# taller_2.net
KiCad netlist of a schematic drawn in EAGLE
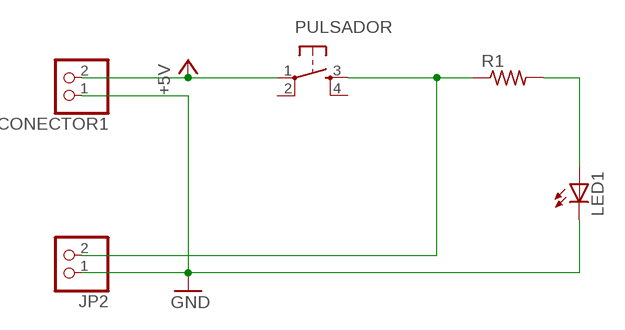
[diagram p0: schematic, sheet 1]

(export (version "E")
  (design (tool "Eeschema 10.0.6"))
  (components
    (comp (ref "CONECTOR1")
      (value "PINHD-1X2/90")
      (footprint "eagle-import:1X02_90")
      (libsource (lib "eagle-import") (part "PINHD-1X2/90"))
    )
    (comp (ref "JP2")
      (value "PINHD-1X2/90")
      (footprint "eagle-import:1X02_90")
      (libsource (lib "eagle-import") (part "PINHD-1X2/90"))
    )
    (comp (ref "LED1")
      (value "LED5MM")
      (footprint "eagle-import:LED5MM")
      (libsource (lib "eagle-import") (part "LED5MM"))
    )
    (comp (ref "PULSADOR")
      (value "TAC_SWITCHPTH")
      (footprint "eagle-import:TACTILE-PTH")
      (libsource (lib "eagle-import") (part "TAC_SWITCHPTH"))
    )
    (comp (ref "R1")
      (value "R-US_0207/12")
      (footprint "eagle-import:0207_12")
      (libsource (lib "eagle-import") (part "R-US_0207/12"))
    )
  )
  (nets
    (net (code "1") (name "+5V") (class "Default")
      (node (ref "CONECTOR1") (pin "2") (pinfunction "2_2") (pintype "passive"))
      (node (ref "PULSADOR") (pin "1") (pinfunction "1_1") (pintype "passive"))
    )
    (net (code "2") (name "GND") (class "Default")
      (node (ref "CONECTOR1") (pin "1") (pinfunction "1_1") (pintype "passive"))
      (node (ref "JP2") (pin "1") (pinfunction "1_1") (pintype "passive"))
      (node (ref "LED1") (pin "K") (pinfunction "C_K") (pintype "passive"))
    )
    (net (code "3") (name "Net-(JP2-Pad2)") (class "Default")
      (node (ref "JP2") (pin "2") (pinfunction "2_2") (pintype "passive"))
      (node (ref "PULSADOR") (pin "3") (pinfunction "3_3") (pintype "passive"))
      (node (ref "R1") (pin "1") (pinfunction "1_1") (pintype "passive"))
    )
    (net (code "4") (name "Net-(LED1-PadA)") (class "Default")
      (node (ref "LED1") (pin "A") (pinfunction "A_A") (pintype "passive"))
      (node (ref "R1") (pin "2") (pinfunction "2_2") (pintype "passive"))
    )
    (net (code "5") (name "unconnected-(PULSADOR-Pad2)") (class "Default")
      (node (ref "PULSADOR") (pin "2") (pinfunction "2_2") (pintype "passive"))
    )
    (net (code "6") (name "unconnected-(PULSADOR-Pad4)") (class "Default")
      (node (ref "PULSADOR") (pin "4") (pinfunction "4_4") (pintype "passive"))
    )
  )
)
